# Oximeter.net
KiCad netlist of a schematic drawn in Altium Designer
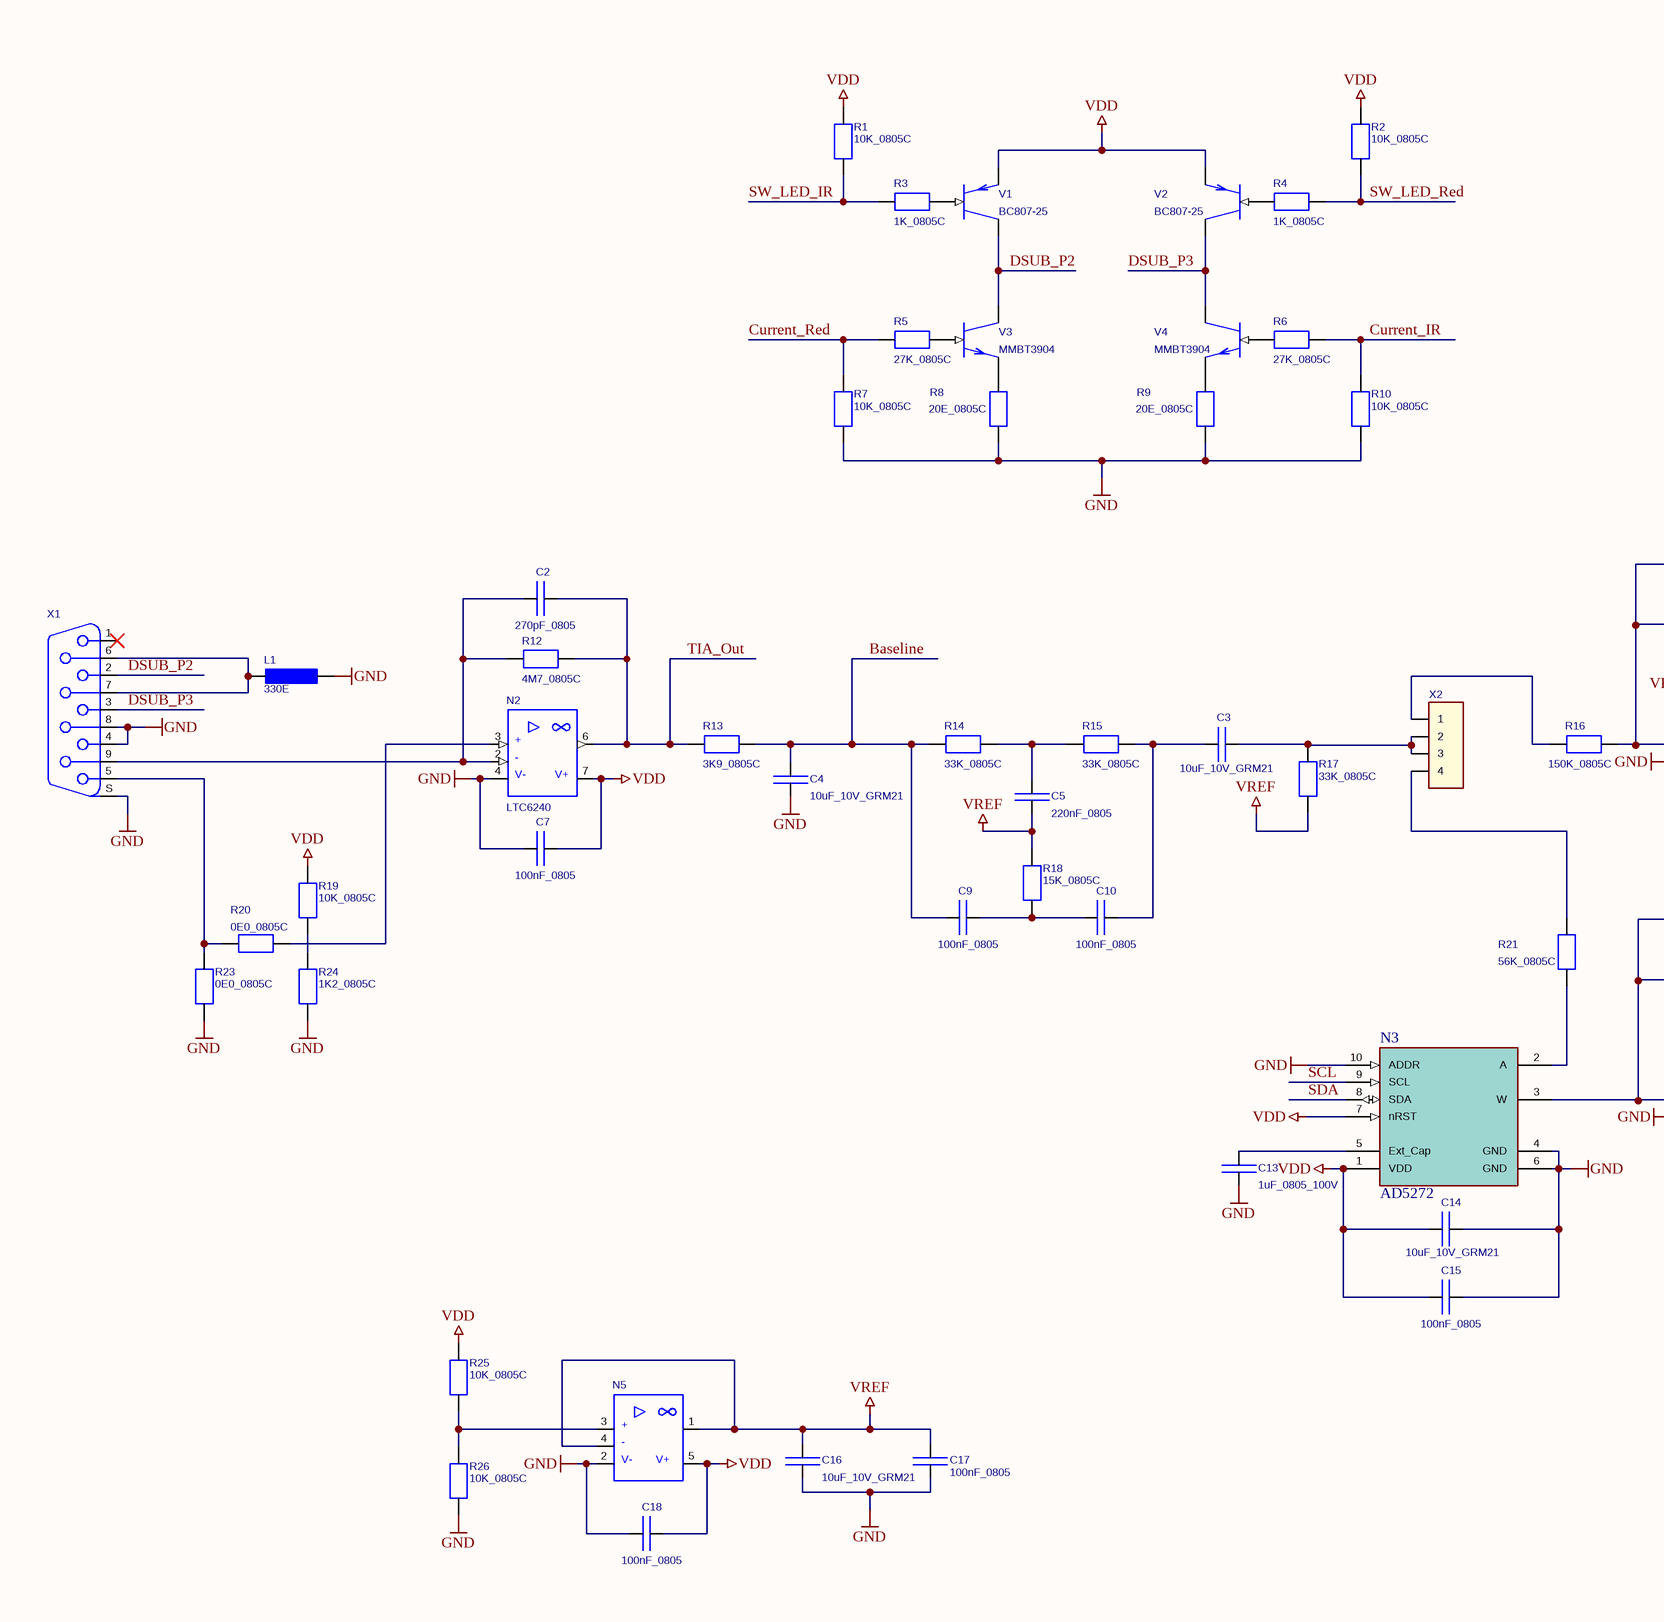
[diagram p0: Oximeter.SchDoc, left]
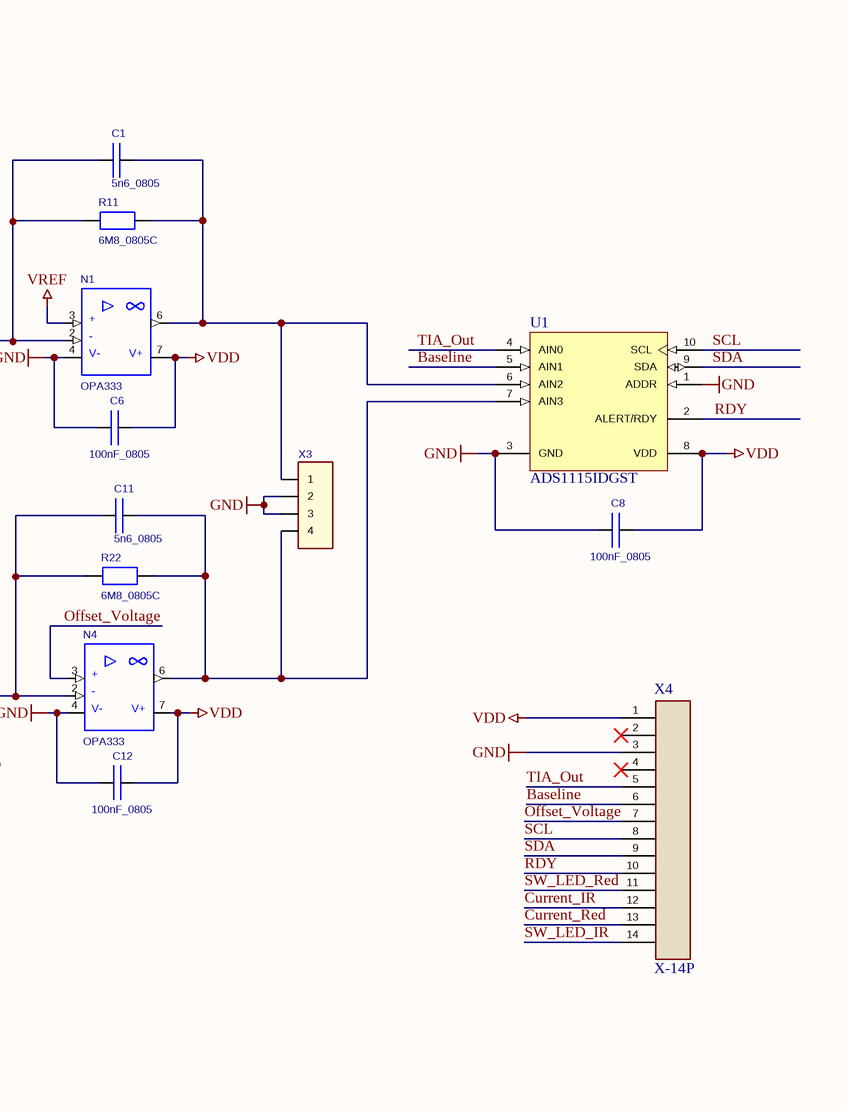
[diagram p1: Oximeter.SchDoc, right]

(export (version "E")
  (design (tool "Eeschema 10.0.6"))
  (components
    (comp (ref "C1")
      (value "5n6_0805")
      (footprint "0805MIL")
      (description "Kond.Keramik SMD Typ X7R 2,2nF B37941-K5222-K60 0805")
      (fields (field (name "PART NUMBER") "2506.1521") (field (name "MANUFACTURER") "Epcos"))
      (libsource (lib "Ruag_D_L") (part "C"))
    )
    (comp (ref "C2")
      (value "270pF_0805")
      (footprint "0805MIL")
      (description "Kond.Keramik Siemens Typ COG SMD 0805")
      (fields (field (name "PART NUMBER") "2506.1509") (field (name "MANUFACTURER") "Siemens"))
      (libsource (lib "Ruag_D_L") (part "C"))
    )
    (comp (ref "C3")
      (value "10uF_10V_GRM21")
      (footprint "0805MIL")
      (description "Monolithic Ceramic Capacitor 10uF/10V GRM21BR61A106KE19L")
      (fields (field (name "PART NUMBER") "2541.8615") (field (name "MANUFACTURER") "MyRata"))
      (libsource (lib "Ruag_D_L") (part "C"))
    )
    (comp (ref "C4")
      (value "10uF_10V_GRM21")
      (footprint "0805MIL")
      (description "Monolithic Ceramic Capacitor 10uF/10V GRM21BR61A106KE19L")
      (fields (field (name "PART NUMBER") "2541.8615") (field (name "MANUFACTURER") "MyRata"))
      (libsource (lib "Ruag_D_L") (part "C"))
    )
    (comp (ref "C5")
      (value "220nF_0805")
      (footprint "0805MIL")
      (description "Kond.Keramik Siemens Typ X7R SMD 0805")
      (fields (field (name "PART NUMBER") "2506.1529") (field (name "MANUFACTURER") "Siemens"))
      (libsource (lib "Ruag_D_L") (part "C"))
    )
    (comp (ref "C6")
      (value "100nF_0805")
      (footprint "0805MIL")
      (description "Kond.Keramik Typ X7R SMD 0805 100nF")
      (fields (field (name "PART NUMBER") "2504.0981") (field (name "MANUFACTURER") "Kemet"))
      (libsource (lib "Ruag_D_L") (part "C"))
    )
    (comp (ref "C7")
      (value "100nF_0805")
      (footprint "0805MIL")
      (description "Kond.Keramik Typ X7R SMD 0805 100nF")
      (fields (field (name "PART NUMBER") "2504.0981") (field (name "MANUFACTURER") "Kemet"))
      (libsource (lib "Ruag_D_L") (part "C"))
    )
    (comp (ref "C8")
      (value "100nF_0805")
      (footprint "0805MIL")
      (description "Kond.Keramik Typ X7R SMD 0805 100nF")
      (fields (field (name "PART NUMBER") "2504.0981") (field (name "MANUFACTURER") "Kemet"))
      (libsource (lib "Ruag_D_L") (part "C"))
    )
    (comp (ref "C9")
      (value "100nF_0805")
      (footprint "0805MIL")
      (description "Kond.Keramik Typ X7R SMD 0805 100nF")
      (fields (field (name "PART NUMBER") "2504.0981") (field (name "MANUFACTURER") "Kemet"))
      (libsource (lib "Ruag_D_L") (part "C"))
    )
    (comp (ref "C10")
      (value "100nF_0805")
      (footprint "0805MIL")
      (description "Kond.Keramik Typ X7R SMD 0805 100nF")
      (fields (field (name "PART NUMBER") "2504.0981") (field (name "MANUFACTURER") "Kemet"))
      (libsource (lib "Ruag_D_L") (part "C"))
    )
    (comp (ref "C11")
      (value "5n6_0805")
      (footprint "0805MIL")
      (description "Kond.Keramik SMD Typ X7R 2,2nF B37941-K5222-K60 0805")
      (fields (field (name "PART NUMBER") "2506.1521") (field (name "MANUFACTURER") "Epcos"))
      (libsource (lib "Ruag_D_L") (part "C"))
    )
    (comp (ref "C12")
      (value "100nF_0805")
      (footprint "0805MIL")
      (description "Kond.Keramik Typ X7R SMD 0805 100nF")
      (fields (field (name "PART NUMBER") "2504.0981") (field (name "MANUFACTURER") "Kemet"))
      (libsource (lib "Ruag_D_L") (part "C"))
    )
    (comp (ref "C13")
      (value "1uF_0805_100V")
      (footprint "0805MIL")
      (description "Kond.Keramik TDK Typ X7S SMD 0805 1uF/100V")
      (fields (field (name "PART NUMBER") "2567.7027") (field (name "MANUFACTURER") "TDK"))
      (libsource (lib "Ruag_D_L") (part "C"))
    )
    (comp (ref "C14")
      (value "10uF_10V_GRM21")
      (footprint "0805MIL")
      (description "Monolithic Ceramic Capacitor 10uF/10V GRM21BR61A106KE19L")
      (fields (field (name "PART NUMBER") "2541.8615") (field (name "MANUFACTURER") "MyRata"))
      (libsource (lib "Ruag_D_L") (part "C"))
    )
    (comp (ref "C15")
      (value "100nF_0805")
      (footprint "0805MIL")
      (description "Kond.Keramik Typ X7R SMD 0805 100nF")
      (fields (field (name "PART NUMBER") "2504.0981") (field (name "MANUFACTURER") "Kemet"))
      (libsource (lib "Ruag_D_L") (part "C"))
    )
    (comp (ref "C16")
      (value "10uF_10V_GRM21")
      (footprint "0805MIL")
      (description "Monolithic Ceramic Capacitor 10uF/10V GRM21BR61A106KE19L")
      (fields (field (name "PART NUMBER") "2541.8615") (field (name "MANUFACTURER") "MyRata"))
      (libsource (lib "Ruag_D_L") (part "C"))
    )
    (comp (ref "C17")
      (value "100nF_0805")
      (footprint "0805MIL")
      (description "Kond.Keramik Typ X7R SMD 0805 100nF")
      (fields (field (name "PART NUMBER") "2504.0981") (field (name "MANUFACTURER") "Kemet"))
      (libsource (lib "Ruag_D_L") (part "C"))
    )
    (comp (ref "C18")
      (value "100nF_0805")
      (footprint "0805MIL")
      (description "Kond.Keramik Typ X7R SMD 0805 100nF")
      (fields (field (name "PART NUMBER") "2504.0981") (field (name "MANUFACTURER") "Kemet"))
      (libsource (lib "Ruag_D_L") (part "C"))
    )
    (comp (ref "L1")
      (value "330E")
      (footprint "0805MIL")
      (description "SMD Ferrit MPZ2012S331A 330Ohm")
      (fields (field (name "PART NUMBER") "2571.6206") (field (name "MANUFACTURER") "TDK"))
      (libsource (lib "Ruag_D_L") (part "SPULE"))
    )
    (comp (ref "N1")
      (value "OPA333")
      (footprint "SOP8_150_65")
      (description "SMD Low Power Precision Op.Amp. OPA211AIDR SOIC8")
      (fields (field (name "PART NUMBER") "2564.2212") (field (name "MANUFACTURER") "Texas Instruments"))
      (libsource (lib "Ruag_D_L") (part "OPA211"))
    )
    (comp (ref "N2")
      (value "LTC6240")
      (footprint "SOP8_150_65")
      (description "SMD Low Power Precision Op.Amp. OPA211AIDR SOIC8")
      (fields (field (name "PART NUMBER") "2564.2212") (field (name "MANUFACTURER") "Texas Instruments"))
      (libsource (lib "Ruag_D_L") (part "OPA211"))
    )
    (comp (ref "N3")
      (value "AD5272")
      (footprint "MSOP10")
      (description "Digitalpotentiometer 1024tap 100k")
      (libsource (lib "LWB_ANA") (part "N-AD5272"))
    )
    (comp (ref "N4")
      (value "OPA333")
      (footprint "SOP8_150_65")
      (description "SMD Low Power Precision Op.Amp. OPA211AIDR SOIC8")
      (fields (field (name "PART NUMBER") "2564.2212") (field (name "MANUFACTURER") "Texas Instruments"))
      (libsource (lib "Ruag_D_L") (part "OPA211"))
    )
    (comp (ref "N5")
      (value "TLV2371IDBVR")
      (footprint "SOT23-5")
      (description "3MHz Rail-to-Rail OpAmp TLV2371IDBVR SOT23-5")
      (fields (field (name "PART NUMBER") "8015.8017") (field (name "MANUFACTURER") "Texas Instruments"))
      (libsource (lib "Ruag_D_L") (part "TLV2371DBV"))
    )
    (comp (ref "R1")
      (value "10K_0805C")
      (footprint "0805MIL")
      (description "Widerst.Chip SMD 1% 0.1W 0805 Serie HMWA 10 kOhm")
      (fields (field (name "PART NUMBER") "2522.1838") (field (name "MANUFACTURER") "Royal Ohm"))
      (libsource (lib "Ruag_D_L") (part "R"))
    )
    (comp (ref "R2")
      (value "10K_0805C")
      (footprint "0805MIL")
      (description "Widerst.Chip SMD 1% 0.1W 0805 Serie HMWA 10 kOhm")
      (fields (field (name "PART NUMBER") "2522.1838") (field (name "MANUFACTURER") "Royal Ohm"))
      (libsource (lib "Ruag_D_L") (part "R"))
    )
    (comp (ref "R3")
      (value "1K_0805C")
      (footprint "0805MIL")
      (description "Widerst.Chip SMD 1% 0.1W 0805 Serie HMWA 1 kOhm")
      (fields (field (name "PART NUMBER") "2522.1806") (field (name "MANUFACTURER") "Royal Ohm"))
      (libsource (lib "Ruag_D_L") (part "R"))
    )
    (comp (ref "R4")
      (value "1K_0805C")
      (footprint "0805MIL")
      (description "Widerst.Chip SMD 1% 0.1W 0805 Serie HMWA 1 kOhm")
      (fields (field (name "PART NUMBER") "2522.1806") (field (name "MANUFACTURER") "Royal Ohm"))
      (libsource (lib "Ruag_D_L") (part "R"))
    )
    (comp (ref "R5")
      (value "27K_0805C")
      (footprint "0805MIL")
      (description "Widerst.Chip SMD 1% 0.1W 0805 Serie HMWA 27 kOhm")
      (fields (field (name "PART NUMBER") "2522.1849") (field (name "MANUFACTURER") "Royal Ohm"))
      (libsource (lib "Ruag_D_L") (part "R"))
    )
    (comp (ref "R6")
      (value "27K_0805C")
      (footprint "0805MIL")
      (description "Widerst.Chip SMD 1% 0.1W 0805 Serie HMWA 27 kOhm")
      (fields (field (name "PART NUMBER") "2522.1849") (field (name "MANUFACTURER") "Royal Ohm"))
      (libsource (lib "Ruag_D_L") (part "R"))
    )
    (comp (ref "R7")
      (value "10K_0805C")
      (footprint "0805MIL")
      (description "Widerst.Chip SMD 1% 0.1W 0805 Serie HMWA 10 kOhm")
      (fields (field (name "PART NUMBER") "2522.1838") (field (name "MANUFACTURER") "Royal Ohm"))
      (libsource (lib "Ruag_D_L") (part "R"))
    )
    (comp (ref "R8")
      (value "20E_0805C")
      (footprint "0805MIL")
      (description "Widerst.Chip SMD 0.1% 0.1W 0805 Serie RN73 20 Ohm")
      (fields (field (name "PART NUMBER") "2544.3651") (field (name "MANUFACTURER") "TYCO/Holsworthy"))
      (libsource (lib "Ruag_D_L") (part "R"))
    )
    (comp (ref "R9")
      (value "20E_0805C")
      (footprint "0805MIL")
      (description "Widerst.Chip SMD 0.1% 0.1W 0805 Serie RN73 20 Ohm")
      (fields (field (name "PART NUMBER") "2544.3651") (field (name "MANUFACTURER") "TYCO/Holsworthy"))
      (libsource (lib "Ruag_D_L") (part "R"))
    )
    (comp (ref "R10")
      (value "10K_0805C")
      (footprint "0805MIL")
      (description "Widerst.Chip SMD 1% 0.1W 0805 Serie HMWA 10 kOhm")
      (fields (field (name "PART NUMBER") "2522.1838") (field (name "MANUFACTURER") "Royal Ohm"))
      (libsource (lib "Ruag_D_L") (part "R"))
    )
    (comp (ref "R11")
      (value "6M8_0805C")
      (footprint "0805MIL")
      (description "Widerst.Chip SMD 1% 0.1W 0805 Serie HMWA 1 MOhm")
      (fields (field (name "PART NUMBER") "2522.1895") (field (name "MANUFACTURER") "Royal Ohm"))
      (libsource (lib "Ruag_D_L") (part "R"))
    )
    (comp (ref "R12")
      (value "4M7_0805C")
      (footprint "0805MIL")
      (description "Widerst.Chip SMD 1% 0.1W 0805 Serie HMWA 1 MOhm")
      (fields (field (name "PART NUMBER") "2522.1895") (field (name "MANUFACTURER") "Royal Ohm"))
      (libsource (lib "Ruag_D_L") (part "R"))
    )
    (comp (ref "R13")
      (value "3K9_0805C")
      (footprint "0805MIL")
      (description "Widerst.Chip SMD 1% 0.1W 0805 Serie HMWA 3,9 kOhm")
      (fields (field (name "PART NUMBER") "2522.1824") (field (name "MANUFACTURER") "Royal Ohm"))
      (libsource (lib "Ruag_D_L") (part "R"))
    )
    (comp (ref "R14")
      (value "33K_0805C")
      (footprint "0805MIL")
      (description "Widerst.Chip SMD 1% 0.1W 0805 Serie HMWA 33 kOhm")
      (fields (field (name "PART NUMBER") "2522.1851") (field (name "MANUFACTURER") "Royal Ohm"))
      (libsource (lib "Ruag_D_L") (part "R"))
    )
    (comp (ref "R15")
      (value "33K_0805C")
      (footprint "0805MIL")
      (description "Widerst.Chip SMD 1% 0.1W 0805 Serie HMWA 33 kOhm")
      (fields (field (name "PART NUMBER") "2522.1851") (field (name "MANUFACTURER") "Royal Ohm"))
      (libsource (lib "Ruag_D_L") (part "R"))
    )
    (comp (ref "R16")
      (value "150K_0805C")
      (footprint "0805MIL")
      (description "Widerst.Chip SMD 1% 0.1W 0805 Serie HMWA 150 kOhm")
      (fields (field (name "PART NUMBER") "2522.1871") (field (name "MANUFACTURER") "Royal Ohm"))
      (libsource (lib "Ruag_D_L") (part "R"))
    )
    (comp (ref "R17")
      (value "33K_0805C")
      (footprint "0805MIL")
      (description "Widerst.Chip SMD 1% 0.1W 0805 Serie HMWA 33 kOhm")
      (fields (field (name "PART NUMBER") "2522.1851") (field (name "MANUFACTURER") "Royal Ohm"))
      (libsource (lib "Ruag_D_L") (part "R"))
    )
    (comp (ref "R18")
      (value "15K_0805C")
      (footprint "0805MIL")
      (description "Widerst.Chip SMD 1% 0.1W 0805 Serie HMWA 15 kOhm")
      (fields (field (name "PART NUMBER") "2522.1843") (field (name "MANUFACTURER") "Royal Ohm"))
      (libsource (lib "Ruag_D_L") (part "R"))
    )
    (comp (ref "R19")
      (value "10K_0805C")
      (footprint "0805MIL")
      (description "Widerst.Chip SMD 1% 0.1W 0805 Serie HMWA 10 kOhm")
      (fields (field (name "PART NUMBER") "2522.1838") (field (name "MANUFACTURER") "Royal Ohm"))
      (libsource (lib "Ruag_D_L") (part "R"))
    )
    (comp (ref "R20")
      (value "0E0_0805C")
      (footprint "0805MIL")
      (description "Widerst.Chip SMD 1% 0.1W 0805 Serie HMWA 0Ohm")
      (fields (field (name "PART NUMBER") "2524.7986") (field (name "MANUFACTURER") "Royal Ohm"))
      (libsource (lib "Ruag_D_L") (part "R"))
    )
    (comp (ref "R21")
      (value "56K_0805C")
      (footprint "0805MIL")
      (description "Widerst.Chip SMD 1% 0.1W 0805 Serie HMWA 56 kOhm")
      (fields (field (name "PART NUMBER") "2522.1858") (field (name "MANUFACTURER") "Royal Ohm"))
      (libsource (lib "Ruag_D_L") (part "R"))
    )
    (comp (ref "R22")
      (value "6M8_0805C")
      (footprint "0805MIL")
      (description "Widerst.Chip SMD 1% 0.1W 0805 Serie HMWA 1 MOhm")
      (fields (field (name "PART NUMBER") "2522.1895") (field (name "MANUFACTURER") "Royal Ohm"))
      (libsource (lib "Ruag_D_L") (part "R"))
    )
    (comp (ref "R23")
      (value "0E0_0805C")
      (footprint "0805MIL")
      (description "Widerst.Chip SMD 1% 0.1W 0805 Serie HMWA 0Ohm")
      (fields (field (name "PART NUMBER") "2524.7986") (field (name "MANUFACTURER") "Royal Ohm"))
      (libsource (lib "Ruag_D_L") (part "R"))
    )
    (comp (ref "R24")
      (value "1K2_0805C")
      (footprint "0805MIL")
      (description "Widerst.Chip SMD 1% 0.1W 0805 Serie HMWA 1,2 kOhm")
      (fields (field (name "PART NUMBER") "2522.1809") (field (name "MANUFACTURER") "Royal Ohm"))
      (libsource (lib "Ruag_D_L") (part "R"))
    )
    (comp (ref "R25")
      (value "10K_0805C")
      (footprint "0805MIL")
      (description "Widerst.Chip SMD 1% 0.1W 0805 Serie HMWA 10 kOhm")
      (fields (field (name "PART NUMBER") "2522.1838") (field (name "MANUFACTURER") "Royal Ohm"))
      (libsource (lib "Ruag_D_L") (part "R"))
    )
    (comp (ref "R26")
      (value "10K_0805C")
      (footprint "0805MIL")
      (description "Widerst.Chip SMD 1% 0.1W 0805 Serie HMWA 10 kOhm")
      (fields (field (name "PART NUMBER") "2522.1838") (field (name "MANUFACTURER") "Royal Ohm"))
      (libsource (lib "Ruag_D_L") (part "R"))
    )
    (comp (ref "U1")
      (value "ADS1115IDGST")
      (footprint "TI-DGS10_N")
      (fields (field (name "MANUFACTURER") "Texas Instruments"))
      (libsource (lib "TI Data Converters Analog to Digital Converter") (part "ADS1115IDGST"))
    )
    (comp (ref "V1")
      (value "BC807-25")
      (footprint "SOT23")
      (description "PNP-Transistor SMD BC807-25 SOT-23")
      (fields (field (name "PART NUMBER") "2110.8189") (field (name "MANUFACTURER") "NXP"))
      (libsource (lib "Ruag_D_L") (part "PNP_2"))
    )
    (comp (ref "V2")
      (value "BC807-25")
      (footprint "SOT23")
      (description "PNP-Transistor SMD BC807-25 SOT-23")
      (fields (field (name "PART NUMBER") "2110.8189") (field (name "MANUFACTURER") "NXP"))
      (libsource (lib "Ruag_D_L") (part "PNP_2"))
    )
    (comp (ref "V3")
      (value "MMBT3904")
      (footprint "SOT23")
      (description "Transistor NPN MMBT3904 SOT-23")
      (fields (field (name "PART NUMBER") "2544.3690") (field (name "MANUFACTURER") "Fairchild"))
      (libsource (lib "Ruag_D_L") (part "NPN_3"))
    )
    (comp (ref "V4")
      (value "MMBT3904")
      (footprint "SOT23")
      (description "Transistor NPN MMBT3904 SOT-23")
      (fields (field (name "PART NUMBER") "2544.3690") (field (name "MANUFACTURER") "Fairchild"))
      (libsource (lib "Ruag_D_L") (part "NPN_3"))
    )
    (comp (ref "X1")
      (value "D-SUB9_S_ABG")
      (footprint "DSUB_9_F_ABG")
      (description "D-SUB 9 Sok 90° mit Winkel und Abstandsbolzen DT09SYC1M63UNB6")
      (fields (field (name "PART NUMBER") "2570.6888") (field (name "MANUFACTURER") "Deltron"))
      (libsource (lib "Ruag_D_L") (part "D-SUB9_P"))
    )
    (comp (ref "X2")
      (value "SL1-053-04G")
      (footprint "SL105304")
      (description "2.54mm Stiftleiste 1reihig 4pol gerade SL1 053 04G")
      (fields (field (name "PART NUMBER") "2552.7782") (field (name "MANUFACTURER") "Fischer"))
      (libsource (lib "Ruag_D_L") (part "STECKER_4P"))
    )
    (comp (ref "X3")
      (value "SL1-053-04G")
      (footprint "SL105304")
      (description "2.54mm Stiftleiste 1reihig 4pol gerade SL1 053 04G")
      (fields (field (name "PART NUMBER") "2552.7782") (field (name "MANUFACTURER") "Fischer"))
      (libsource (lib "Ruag_D_L") (part "STECKER_4P"))
    )
    (comp (ref "X4")
      (value "X-14P")
      (footprint "SIP14")
      (description "Stiftenleiste 14 pin")
      (libsource (lib "LWB_ELM") (part "X-14P"))
    )
  )
  (nets
    (net (code "1") (name "/Baseline") (class "Default")
      (node (ref "C4") (pin "1") (pinfunction "1_1") (pintype "passive"))
      (node (ref "C9") (pin "1") (pinfunction "1_1") (pintype "passive"))
      (node (ref "R13") (pin "1") (pinfunction "1_1") (pintype "passive"))
      (node (ref "R14") (pin "2") (pinfunction "2_2") (pintype "passive"))
      (node (ref "U1") (pin "5") (pinfunction "AIN1_5") (pintype "input"))
      (node (ref "X4") (pin "6") (pinfunction "6_6") (pintype "passive"))
    )
    (net (code "2") (name "/Current_IR") (class "Default")
      (node (ref "R10") (pin "1") (pinfunction "1_1") (pintype "passive"))
      (node (ref "R6") (pin "1") (pinfunction "1_1") (pintype "passive"))
      (node (ref "X4") (pin "12") (pinfunction "12_12") (pintype "passive"))
    )
    (net (code "3") (name "/Current_Red") (class "Default")
      (node (ref "R5") (pin "2") (pinfunction "2_2") (pintype "passive"))
      (node (ref "R7") (pin "1") (pinfunction "1_1") (pintype "passive"))
      (node (ref "X4") (pin "13") (pinfunction "13_13") (pintype "passive"))
    )
    (net (code "4") (name "/DSUB_P2") (class "Default")
      (node (ref "V1") (pin "3") (pinfunction "3_3") (pintype "passive"))
      (node (ref "V3") (pin "3") (pinfunction "C_3") (pintype "passive"))
      (node (ref "X1") (pin "2") (pinfunction "2_2") (pintype "passive"))
    )
    (net (code "5") (name "/DSUB_P3") (class "Default")
      (node (ref "V2") (pin "3") (pinfunction "3_3") (pintype "passive"))
      (node (ref "V4") (pin "3") (pinfunction "C_3") (pintype "passive"))
      (node (ref "X1") (pin "3") (pinfunction "3_3") (pintype "passive"))
    )
    (net (code "6") (name "/Offset_Voltage") (class "Default")
      (node (ref "N4") (pin "3") (pinfunction "IN1+_3") (pintype "input"))
      (node (ref "X4") (pin "7") (pinfunction "7_7") (pintype "passive"))
    )
    (net (code "7") (name "/RDY") (class "Default")
      (node (ref "U1") (pin "2") (pinfunction "ALERT/RDY_2") (pintype "open_collector"))
      (node (ref "X4") (pin "10") (pinfunction "10_10") (pintype "passive"))
    )
    (net (code "8") (name "/SCL") (class "Default")
      (node (ref "N3") (pin "9") (pinfunction "SCL_9") (pintype "input"))
      (node (ref "U1") (pin "10") (pinfunction "SCL_10") (pintype "input"))
      (node (ref "X4") (pin "8") (pinfunction "8_8") (pintype "passive"))
    )
    (net (code "9") (name "/SDA") (class "Default")
      (node (ref "N3") (pin "8") (pinfunction "SDA_8") (pintype "bidirectional"))
      (node (ref "U1") (pin "9") (pinfunction "SDA_9") (pintype "bidirectional"))
      (node (ref "X4") (pin "9") (pinfunction "9_9") (pintype "passive"))
    )
    (net (code "10") (name "/SW_LED_IR") (class "Default")
      (node (ref "R1") (pin "2") (pinfunction "2_2") (pintype "passive"))
      (node (ref "R3") (pin "2") (pinfunction "2_2") (pintype "passive"))
      (node (ref "X4") (pin "14") (pinfunction "14_14") (pintype "passive"))
    )
    (net (code "11") (name "/SW_LED_Red") (class "Default")
      (node (ref "R2") (pin "2") (pinfunction "2_2") (pintype "passive"))
      (node (ref "R4") (pin "1") (pinfunction "1_1") (pintype "passive"))
      (node (ref "X4") (pin "11") (pinfunction "11_11") (pintype "passive"))
    )
    (net (code "12") (name "/TIA_Out") (class "Default")
      (node (ref "C2") (pin "2") (pinfunction "2_2") (pintype "passive"))
      (node (ref "N2") (pin "6") (pinfunction "Out1_6") (pintype "output"))
      (node (ref "R12") (pin "1") (pinfunction "1_1") (pintype "passive"))
      (node (ref "R13") (pin "2") (pinfunction "2_2") (pintype "passive"))
      (node (ref "U1") (pin "4") (pinfunction "AIN0_4") (pintype "input"))
      (node (ref "X4") (pin "5") (pinfunction "5_5") (pintype "passive"))
    )
    (net (code "13") (name "GND") (class "Default")
      (node (ref "C12") (pin "1") (pinfunction "1_1") (pintype "passive"))
      (node (ref "C13") (pin "2") (pinfunction "2_2") (pintype "passive"))
      (node (ref "C14") (pin "2") (pinfunction "2_2") (pintype "passive"))
      (node (ref "C15") (pin "2") (pinfunction "2_2") (pintype "passive"))
      (node (ref "C16") (pin "2") (pinfunction "2_2") (pintype "passive"))
      (node (ref "C17") (pin "1") (pinfunction "1_1") (pintype "passive"))
      (node (ref "C18") (pin "1") (pinfunction "1_1") (pintype "passive"))
      (node (ref "C4") (pin "2") (pinfunction "2_2") (pintype "passive"))
      (node (ref "C6") (pin "1") (pinfunction "1_1") (pintype "passive"))
      (node (ref "C7") (pin "1") (pinfunction "1_1") (pintype "passive"))
      (node (ref "C8") (pin "1") (pinfunction "1_1") (pintype "passive"))
      (node (ref "L1") (pin "2") (pinfunction "2_2") (pintype "passive"))
      (node (ref "N1") (pin "4") (pinfunction "V-_4") (pintype "passive"))
      (node (ref "N2") (pin "4") (pinfunction "V-_4") (pintype "passive"))
      (node (ref "N3") (pin "10") (pinfunction "ADDR_10") (pintype "input"))
      (node (ref "N3") (pin "4") (pinfunction "GND_4") (pintype "power_in"))
      (node (ref "N3") (pin "6") (pinfunction "GND_6") (pintype "power_in"))
      (node (ref "N4") (pin "4") (pinfunction "V-_4") (pintype "passive"))
      (node (ref "N5") (pin "2") (pinfunction "GND_2") (pintype "passive"))
      (node (ref "R10") (pin "2") (pinfunction "2_2") (pintype "passive"))
      (node (ref "R23") (pin "2") (pinfunction "2_2") (pintype "passive"))
      (node (ref "R24") (pin "2") (pinfunction "2_2") (pintype "passive"))
      (node (ref "R26") (pin "2") (pinfunction "2_2") (pintype "passive"))
      (node (ref "R7") (pin "2") (pinfunction "2_2") (pintype "passive"))
      (node (ref "R8") (pin "2") (pinfunction "2_2") (pintype "passive"))
      (node (ref "R9") (pin "2") (pinfunction "2_2") (pintype "passive"))
      (node (ref "U1") (pin "1") (pinfunction "ADDR_1") (pintype "input"))
      (node (ref "U1") (pin "3") (pinfunction "GND_3") (pintype "power_in"))
      (node (ref "X1") (pin "4") (pinfunction "4_4") (pintype "passive"))
      (node (ref "X1") (pin "8") (pinfunction "8_8") (pintype "passive"))
      (node (ref "X1") (pin "S") (pinfunction "S_S") (pintype "passive"))
      (node (ref "X3") (pin "2") (pinfunction "2_2") (pintype "passive"))
      (node (ref "X3") (pin "3") (pinfunction "3_3") (pintype "passive"))
      (node (ref "X4") (pin "3") (pinfunction "3_3") (pintype "passive"))
    )
    (net (code "14") (name "Net-(C3-Pad2)") (class "Default")
      (node (ref "C3") (pin "2") (pinfunction "2_2") (pintype "passive"))
      (node (ref "R17") (pin "1") (pinfunction "1_1") (pintype "passive"))
      (node (ref "X2") (pin "2") (pinfunction "2_2") (pintype "passive"))
      (node (ref "X2") (pin "3") (pinfunction "3_3") (pintype "passive"))
    )
    (net (code "15") (name "Net-(C5-Pad1)") (class "Default")
      (node (ref "C5") (pin "1") (pinfunction "1_1") (pintype "passive"))
      (node (ref "R14") (pin "1") (pinfunction "1_1") (pintype "passive"))
      (node (ref "R15") (pin "2") (pinfunction "2_2") (pintype "passive"))
    )
    (net (code "16") (name "Net-(C10-Pad1)") (class "Default")
      (node (ref "C10") (pin "1") (pinfunction "1_1") (pintype "passive"))
      (node (ref "C9") (pin "2") (pinfunction "2_2") (pintype "passive"))
      (node (ref "R18") (pin "2") (pinfunction "2_2") (pintype "passive"))
    )
    (net (code "17") (name "Net-(C10-Pad2)") (class "Default")
      (node (ref "C10") (pin "2") (pinfunction "2_2") (pintype "passive"))
      (node (ref "C3") (pin "1") (pinfunction "1_1") (pintype "passive"))
      (node (ref "R15") (pin "1") (pinfunction "1_1") (pintype "passive"))
    )
    (net (code "18") (name "Net-(L1-Pad1)") (class "Default")
      (node (ref "L1") (pin "1") (pinfunction "1_1") (pintype "passive"))
      (node (ref "X1") (pin "6") (pinfunction "6_6") (pintype "passive"))
      (node (ref "X1") (pin "7") (pinfunction "7_7") (pintype "passive"))
    )
    (net (code "19") (name "Net-(N1-IN1-)") (class "Default")
      (node (ref "C1") (pin "1") (pinfunction "1_1") (pintype "passive"))
      (node (ref "N1") (pin "2") (pinfunction "IN1-_2") (pintype "input"))
      (node (ref "R11") (pin "2") (pinfunction "2_2") (pintype "passive"))
      (node (ref "R16") (pin "1") (pinfunction "1_1") (pintype "passive"))
    )
    (net (code "20") (name "Net-(N1-Out1)") (class "Default")
      (node (ref "C1") (pin "2") (pinfunction "2_2") (pintype "passive"))
      (node (ref "N1") (pin "6") (pinfunction "Out1_6") (pintype "output"))
      (node (ref "R11") (pin "1") (pinfunction "1_1") (pintype "passive"))
      (node (ref "U1") (pin "6") (pinfunction "AIN2_6") (pintype "input"))
      (node (ref "X3") (pin "1") (pinfunction "1_1") (pintype "passive"))
    )
    (net (code "21") (name "Net-(N2-IN1+)") (class "Default")
      (node (ref "N2") (pin "3") (pinfunction "IN1+_3") (pintype "input"))
      (node (ref "R20") (pin "1") (pinfunction "1_1") (pintype "passive"))
    )
    (net (code "22") (name "Net-(N2-IN1-)") (class "Default")
      (node (ref "C2") (pin "1") (pinfunction "1_1") (pintype "passive"))
      (node (ref "N2") (pin "2") (pinfunction "IN1-_2") (pintype "input"))
      (node (ref "R12") (pin "2") (pinfunction "2_2") (pintype "passive"))
      (node (ref "X1") (pin "9") (pinfunction "9_9") (pintype "passive"))
    )
    (net (code "23") (name "Net-(N3-A)") (class "Default")
      (node (ref "N3") (pin "2") (pinfunction "A_2") (pintype "passive"))
      (node (ref "R21") (pin "2") (pinfunction "2_2") (pintype "passive"))
    )
    (net (code "24") (name "Net-(N3-Ext_Cap)") (class "Default")
      (node (ref "C13") (pin "1") (pinfunction "1_1") (pintype "passive"))
      (node (ref "N3") (pin "5") (pinfunction "Ext_Cap_5") (pintype "power_in"))
    )
    (net (code "25") (name "Net-(N3-W)") (class "Default")
      (node (ref "C11") (pin "1") (pinfunction "1_1") (pintype "passive"))
      (node (ref "N3") (pin "3") (pinfunction "W_3") (pintype "passive"))
      (node (ref "N4") (pin "2") (pinfunction "IN1-_2") (pintype "input"))
      (node (ref "R22") (pin "2") (pinfunction "2_2") (pintype "passive"))
    )
    (net (code "26") (name "Net-(N4-Out1)") (class "Default")
      (node (ref "C11") (pin "2") (pinfunction "2_2") (pintype "passive"))
      (node (ref "N4") (pin "6") (pinfunction "Out1_6") (pintype "output"))
      (node (ref "R22") (pin "1") (pinfunction "1_1") (pintype "passive"))
      (node (ref "U1") (pin "7") (pinfunction "AIN3_7") (pintype "input"))
      (node (ref "X3") (pin "4") (pinfunction "4_4") (pintype "passive"))
    )
    (net (code "27") (name "Net-(N5-PLUS_INPUT)") (class "Default")
      (node (ref "N5") (pin "3") (pinfunction "PLUS_INPUT_3") (pintype "passive"))
      (node (ref "R25") (pin "2") (pinfunction "2_2") (pintype "passive"))
      (node (ref "R26") (pin "1") (pinfunction "1_1") (pintype "passive"))
    )
    (net (code "28") (name "Net-(R3-Pad1)") (class "Default")
      (node (ref "R3") (pin "1") (pinfunction "1_1") (pintype "passive"))
      (node (ref "V1") (pin "1") (pinfunction "1_1") (pintype "input"))
    )
    (net (code "29") (name "Net-(R4-Pad2)") (class "Default")
      (node (ref "R4") (pin "2") (pinfunction "2_2") (pintype "passive"))
      (node (ref "V2") (pin "1") (pinfunction "1_1") (pintype "input"))
    )
    (net (code "30") (name "Net-(R16-Pad2)") (class "Default")
      (node (ref "R16") (pin "2") (pinfunction "2_2") (pintype "passive"))
      (node (ref "X2") (pin "1") (pinfunction "1_1") (pintype "passive"))
    )
    (net (code "31") (name "Net-(R19-Pad2)") (class "Default")
      (node (ref "R19") (pin "2") (pinfunction "2_2") (pintype "passive"))
      (node (ref "R24") (pin "1") (pinfunction "1_1") (pintype "passive"))
    )
    (net (code "32") (name "Net-(R20-Pad2)") (class "Default")
      (node (ref "R20") (pin "2") (pinfunction "2_2") (pintype "passive"))
      (node (ref "R23") (pin "1") (pinfunction "1_1") (pintype "passive"))
      (node (ref "X1") (pin "5") (pinfunction "5_5") (pintype "passive"))
    )
    (net (code "33") (name "Net-(R21-Pad1)") (class "Default")
      (node (ref "R21") (pin "1") (pinfunction "1_1") (pintype "passive"))
      (node (ref "X2") (pin "4") (pinfunction "4_4") (pintype "passive"))
    )
    (net (code "34") (name "Net-(V3-B)") (class "Default")
      (node (ref "R5") (pin "1") (pinfunction "1_1") (pintype "passive"))
      (node (ref "V3") (pin "1") (pinfunction "B_1") (pintype "input"))
    )
    (net (code "35") (name "Net-(V3-E)") (class "Default")
      (node (ref "R8") (pin "1") (pinfunction "1_1") (pintype "passive"))
      (node (ref "V3") (pin "2") (pinfunction "E_2") (pintype "passive"))
    )
    (net (code "36") (name "Net-(V4-B)") (class "Default")
      (node (ref "R6") (pin "2") (pinfunction "2_2") (pintype "passive"))
      (node (ref "V4") (pin "1") (pinfunction "B_1") (pintype "input"))
    )
    (net (code "37") (name "Net-(V4-E)") (class "Default")
      (node (ref "R9") (pin "1") (pinfunction "1_1") (pintype "passive"))
      (node (ref "V4") (pin "2") (pinfunction "E_2") (pintype "passive"))
    )
    (net (code "38") (name "VDD") (class "Default")
      (node (ref "C12") (pin "2") (pinfunction "2_2") (pintype "passive"))
      (node (ref "C14") (pin "1") (pinfunction "1_1") (pintype "passive"))
      (node (ref "C15") (pin "1") (pinfunction "1_1") (pintype "passive"))
      (node (ref "C18") (pin "2") (pinfunction "2_2") (pintype "passive"))
      (node (ref "C6") (pin "2") (pinfunction "2_2") (pintype "passive"))
      (node (ref "C7") (pin "2") (pinfunction "2_2") (pintype "passive"))
      (node (ref "C8") (pin "2") (pinfunction "2_2") (pintype "passive"))
      (node (ref "N1") (pin "7") (pinfunction "V+_7") (pintype "passive"))
      (node (ref "N2") (pin "7") (pinfunction "V+_7") (pintype "passive"))
      (node (ref "N3") (pin "1") (pinfunction "VDD_1") (pintype "power_in"))
      (node (ref "N3") (pin "7") (pinfunction "nRST_7") (pintype "input"))
      (node (ref "N4") (pin "7") (pinfunction "V+_7") (pintype "passive"))
      (node (ref "N5") (pin "5") (pinfunction "VDD_5") (pintype "passive"))
      (node (ref "R1") (pin "1") (pinfunction "1_1") (pintype "passive"))
      (node (ref "R19") (pin "1") (pinfunction "1_1") (pintype "passive"))
      (node (ref "R2") (pin "1") (pinfunction "1_1") (pintype "passive"))
      (node (ref "R25") (pin "1") (pinfunction "1_1") (pintype "passive"))
      (node (ref "U1") (pin "8") (pinfunction "VDD_8") (pintype "power_in"))
      (node (ref "V1") (pin "2") (pinfunction "2_2") (pintype "passive"))
      (node (ref "V2") (pin "2") (pinfunction "2_2") (pintype "passive"))
      (node (ref "X4") (pin "1") (pinfunction "1_1") (pintype "passive"))
    )
    (net (code "39") (name "VREF") (class "Default")
      (node (ref "C16") (pin "1") (pinfunction "1_1") (pintype "passive"))
      (node (ref "C17") (pin "2") (pinfunction "2_2") (pintype "passive"))
      (node (ref "C5") (pin "2") (pinfunction "2_2") (pintype "passive"))
      (node (ref "N1") (pin "3") (pinfunction "IN1+_3") (pintype "input"))
      (node (ref "N5") (pin "1") (pinfunction "OUTPUT_1") (pintype "passive"))
      (node (ref "N5") (pin "4") (pinfunction "MINUS_INPUT_4") (pintype "passive"))
      (node (ref "R17") (pin "2") (pinfunction "2_2") (pintype "passive"))
      (node (ref "R18") (pin "1") (pinfunction "1_1") (pintype "passive"))
    )
    (net (code "40") (name "unconnected-(X1-Pad1)") (class "Default")
      (node (ref "X1") (pin "1") (pinfunction "1_1") (pintype "passive+no_connect"))
    )
    (net (code "41") (name "unconnected-(X4-Pad2)") (class "Default")
      (node (ref "X4") (pin "2") (pinfunction "2_2") (pintype "passive+no_connect"))
    )
    (net (code "42") (name "unconnected-(X4-Pad4)") (class "Default")
      (node (ref "X4") (pin "4") (pinfunction "4_4") (pintype "passive+no_connect"))
    )
  )
)
